# v1_0_r1.net
KiCad netlist of a schematic drawn in EAGLE
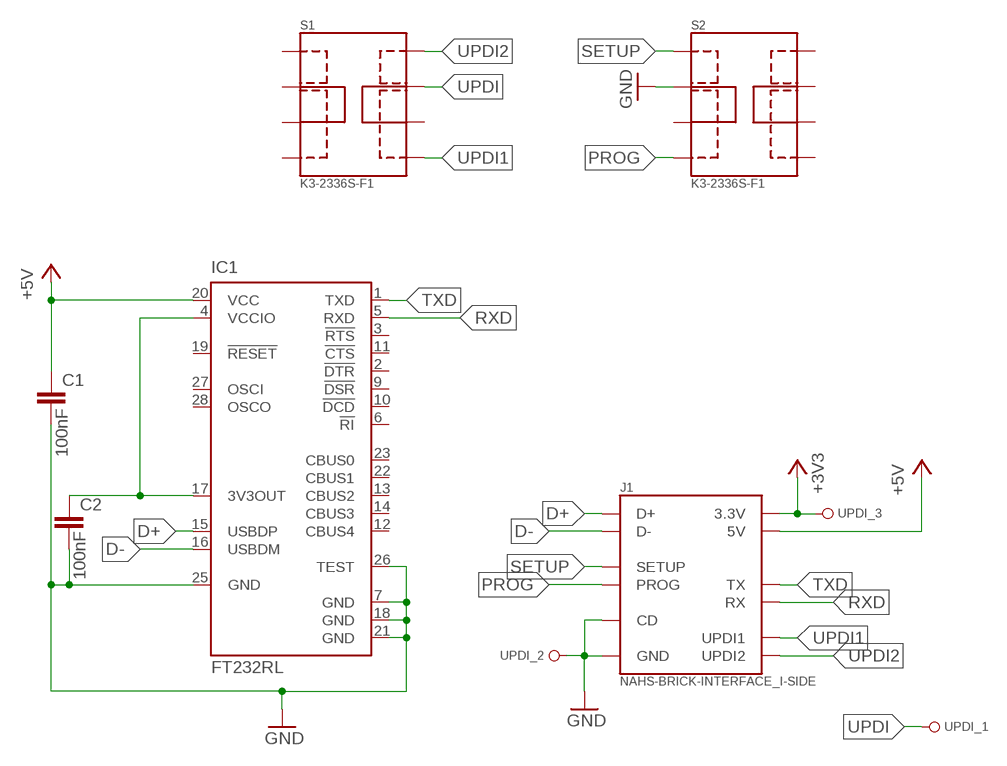
[diagram p0: schematic, sheet 1]

(export (version "E")
  (design (tool "Eeschema 10.0.6"))
  (components
    (comp (ref "C1")
      (value "100nF")
      (footprint "eagle-import:C0805")
      (libsource (lib "eagle-import") (part "C-EUC0805"))
    )
    (comp (ref "C2")
      (value "100nF")
      (footprint "eagle-import:C0805")
      (libsource (lib "eagle-import") (part "C-EUC0805"))
    )
    (comp (ref "IC1")
      (value "FT232RL")
      (footprint "eagle-import:SSOP28")
      (libsource (lib "eagle-import") (part "FT232RL"))
    )
    (comp (ref "J1")
      (value "NAHS-BRICK-INTERFACE_I-SIDE")
      (footprint "eagle-import:54102-0164")
      (libsource (lib "eagle-import") (part "NAHS-BRICK-INTERFACE_I-SIDE"))
    )
    (comp (ref "S1")
      (value "K3-2336S-F1")
      (footprint "eagle-import:K3-2336S-F1")
      (libsource (lib "eagle-import") (part "K3-2336S-F1"))
    )
    (comp (ref "S2")
      (value "K3-2336S-F1")
      (footprint "eagle-import:K3-2336S-F1")
      (libsource (lib "eagle-import") (part "K3-2336S-F1"))
    )
    (comp (ref "UPDI")
      (value "PINHD_1X03_R_1")
      (footprint "eagle-import:1X03_R_1")
      (libsource (lib "eagle-import") (part "PINHD_1X03_R_1"))
    )
  )
  (nets
    (net (code "1") (name "+3V3") (class "Default")
      (node (ref "J1") (pin "16") (pinfunction "3.3V_16") (pintype "bidirectional"))
      (node (ref "UPDI") (pin "3") (pinfunction "1_3") (pintype "bidirectional"))
    )
    (net (code "2") (name "+5V") (class "Default")
      (node (ref "C1") (pin "1") (pinfunction "1_1") (pintype "passive"))
      (node (ref "IC1") (pin "20") (pinfunction "VCC_20") (pintype "power_in"))
      (node (ref "J1") (pin "5") (pinfunction "5V_5") (pintype "bidirectional"))
      (node (ref "J1") (pin "6") (pinfunction "5V_6") (pintype "bidirectional"))
    )
    (net (code "3") (name "D+") (class "Default")
      (node (ref "IC1") (pin "15") (pinfunction "USBDP_15") (pintype "bidirectional"))
      (node (ref "J1") (pin "9") (pinfunction "D+_9") (pintype "bidirectional"))
    )
    (net (code "4") (name "D-") (class "Default")
      (node (ref "IC1") (pin "16") (pinfunction "USBDM_16") (pintype "bidirectional"))
      (node (ref "J1") (pin "10") (pinfunction "D-_10") (pintype "bidirectional"))
    )
    (net (code "5") (name "GND") (class "Default")
      (node (ref "C1") (pin "2") (pinfunction "2_2") (pintype "passive"))
      (node (ref "C2") (pin "2") (pinfunction "2_2") (pintype "passive"))
      (node (ref "IC1") (pin "18") (pinfunction "GND_18") (pintype "power_in"))
      (node (ref "IC1") (pin "21") (pinfunction "GND_21") (pintype "power_in"))
      (node (ref "IC1") (pin "25") (pinfunction "GND_25") (pintype "power_in"))
      (node (ref "IC1") (pin "26") (pinfunction "TEST_26") (pintype "input"))
      (node (ref "IC1") (pin "7") (pinfunction "GND_7") (pintype "power_in"))
      (node (ref "J1") (pin "11") (pinfunction "GND_11") (pintype "bidirectional"))
      (node (ref "J1") (pin "12") (pinfunction "GND_12") (pintype "bidirectional"))
      (node (ref "J1") (pin "13") (pinfunction "CD_13") (pintype "bidirectional"))
      (node (ref "S2") (pin "1.2") (pinfunction "1.2_1.2") (pintype "bidirectional"))
      (node (ref "UPDI") (pin "2") (pinfunction "1_2") (pintype "bidirectional"))
    )
    (net (code "6") (name "Net-(IC1-3V3OUT)") (class "Default")
      (node (ref "C2") (pin "1") (pinfunction "1_1") (pintype "passive"))
      (node (ref "IC1") (pin "17") (pinfunction "3V3OUT_17") (pintype "output"))
      (node (ref "IC1") (pin "4") (pinfunction "VCCIO_4") (pintype "power_in"))
    )
    (net (code "7") (name "PROG") (class "Default")
      (node (ref "J1") (pin "1") (pinfunction "PROG_1") (pintype "bidirectional"))
      (node (ref "S2") (pin "1.4") (pinfunction "1.4_1.4") (pintype "bidirectional"))
    )
    (net (code "8") (name "RXD") (class "Default")
      (node (ref "IC1") (pin "5") (pinfunction "RXD_5") (pintype "input"))
      (node (ref "J1") (pin "7") (pinfunction "RX_7") (pintype "bidirectional"))
    )
    (net (code "9") (name "SETUP") (class "Default")
      (node (ref "J1") (pin "2") (pinfunction "SETUP_2") (pintype "bidirectional"))
      (node (ref "S2") (pin "1.1") (pinfunction "1.1_1.1") (pintype "bidirectional"))
    )
    (net (code "10") (name "TXD") (class "Default")
      (node (ref "IC1") (pin "1") (pinfunction "TXD_1") (pintype "output"))
      (node (ref "J1") (pin "8") (pinfunction "TX_8") (pintype "bidirectional"))
    )
    (net (code "11") (name "UPDI") (class "Default")
      (node (ref "S1") (pin "2.2") (pinfunction "2.2_2.2") (pintype "bidirectional"))
      (node (ref "UPDI") (pin "1") (pinfunction "1_1") (pintype "bidirectional"))
    )
    (net (code "12") (name "UPDI1") (class "Default")
      (node (ref "J1") (pin "15") (pinfunction "UPDI1_15") (pintype "bidirectional"))
      (node (ref "S1") (pin "2.4") (pinfunction "2.4_2.4") (pintype "bidirectional"))
    )
    (net (code "13") (name "UPDI2") (class "Default")
      (node (ref "J1") (pin "14") (pinfunction "UPDI2_14") (pintype "bidirectional"))
      (node (ref "S1") (pin "2.1") (pinfunction "2.1_2.1") (pintype "bidirectional"))
    )
    (net (code "14") (name "unconnected-(IC1-CBUS0-Pad23)") (class "Default")
      (node (ref "IC1") (pin "23") (pinfunction "CBUS0_23") (pintype "bidirectional"))
    )
    (net (code "15") (name "unconnected-(IC1-CBUS1-Pad22)") (class "Default")
      (node (ref "IC1") (pin "22") (pinfunction "CBUS1_22") (pintype "bidirectional"))
    )
    (net (code "16") (name "unconnected-(IC1-CBUS2-Pad13)") (class "Default")
      (node (ref "IC1") (pin "13") (pinfunction "CBUS2_13") (pintype "bidirectional"))
    )
    (net (code "17") (name "unconnected-(IC1-CBUS3-Pad14)") (class "Default")
      (node (ref "IC1") (pin "14") (pinfunction "CBUS3_14") (pintype "bidirectional"))
    )
    (net (code "18") (name "unconnected-(IC1-CBUS4-Pad12)") (class "Default")
      (node (ref "IC1") (pin "12") (pinfunction "CBUS4_12") (pintype "bidirectional"))
    )
    (net (code "19") (name "unconnected-(IC1-OSCI-Pad27)") (class "Default")
      (node (ref "IC1") (pin "27") (pinfunction "OSCI_27") (pintype "input"))
    )
    (net (code "20") (name "unconnected-(IC1-OSCO-Pad28)") (class "Default")
      (node (ref "IC1") (pin "28") (pinfunction "OSCO_28") (pintype "output"))
    )
    (net (code "21") (name "unconnected-(IC1-~{CTS}-Pad11)") (class "Default")
      (node (ref "IC1") (pin "11") (pinfunction "~{CTS}_11") (pintype "input"))
    )
    (net (code "22") (name "unconnected-(IC1-~{DCD}-Pad10)") (class "Default")
      (node (ref "IC1") (pin "10") (pinfunction "~{DCD}_10") (pintype "input"))
    )
    (net (code "23") (name "unconnected-(IC1-~{DSR}-Pad9)") (class "Default")
      (node (ref "IC1") (pin "9") (pinfunction "~{DSR}_9") (pintype "input"))
    )
    (net (code "24") (name "unconnected-(IC1-~{DTR}-Pad2)") (class "Default")
      (node (ref "IC1") (pin "2") (pinfunction "~{DTR}_2") (pintype "output"))
    )
    (net (code "25") (name "unconnected-(IC1-~{RESET}-Pad19)") (class "Default")
      (node (ref "IC1") (pin "19") (pinfunction "~{RESET}_19") (pintype "input"))
    )
    (net (code "26") (name "unconnected-(IC1-~{RI}-Pad6)") (class "Default")
      (node (ref "IC1") (pin "6") (pinfunction "~{RI}_6") (pintype "input"))
    )
    (net (code "27") (name "unconnected-(IC1-~{RTS}-Pad3)") (class "Default")
      (node (ref "IC1") (pin "3") (pinfunction "~{RTS}_3") (pintype "output"))
    )
    (net (code "28") (name "unconnected-(S1-Pad1.1)") (class "Default")
      (node (ref "S1") (pin "1.1") (pinfunction "1.1_1.1") (pintype "bidirectional"))
    )
    (net (code "29") (name "unconnected-(S1-Pad1.2)") (class "Default")
      (node (ref "S1") (pin "1.2") (pinfunction "1.2_1.2") (pintype "bidirectional"))
    )
    (net (code "30") (name "unconnected-(S1-Pad1.3)") (class "Default")
      (node (ref "S1") (pin "1.3") (pinfunction "1.3_1.3") (pintype "bidirectional"))
    )
    (net (code "31") (name "unconnected-(S1-Pad1.4)") (class "Default")
      (node (ref "S1") (pin "1.4") (pinfunction "1.4_1.4") (pintype "bidirectional"))
    )
    (net (code "32") (name "unconnected-(S1-Pad2.3)") (class "Default")
      (node (ref "S1") (pin "2.3") (pinfunction "2.3_2.3") (pintype "bidirectional"))
    )
    (net (code "33") (name "unconnected-(S2-Pad1.3)") (class "Default")
      (node (ref "S2") (pin "1.3") (pinfunction "1.3_1.3") (pintype "bidirectional"))
    )
    (net (code "34") (name "unconnected-(S2-Pad2.1)") (class "Default")
      (node (ref "S2") (pin "2.1") (pinfunction "2.1_2.1") (pintype "bidirectional"))
    )
    (net (code "35") (name "unconnected-(S2-Pad2.2)") (class "Default")
      (node (ref "S2") (pin "2.2") (pinfunction "2.2_2.2") (pintype "bidirectional"))
    )
    (net (code "36") (name "unconnected-(S2-Pad2.3)") (class "Default")
      (node (ref "S2") (pin "2.3") (pinfunction "2.3_2.3") (pintype "bidirectional"))
    )
    (net (code "37") (name "unconnected-(S2-Pad2.4)") (class "Default")
      (node (ref "S2") (pin "2.4") (pinfunction "2.4_2.4") (pintype "bidirectional"))
    )
  )
)
